# Sheet1.net
KiCad netlist of a schematic drawn in Altium Designer
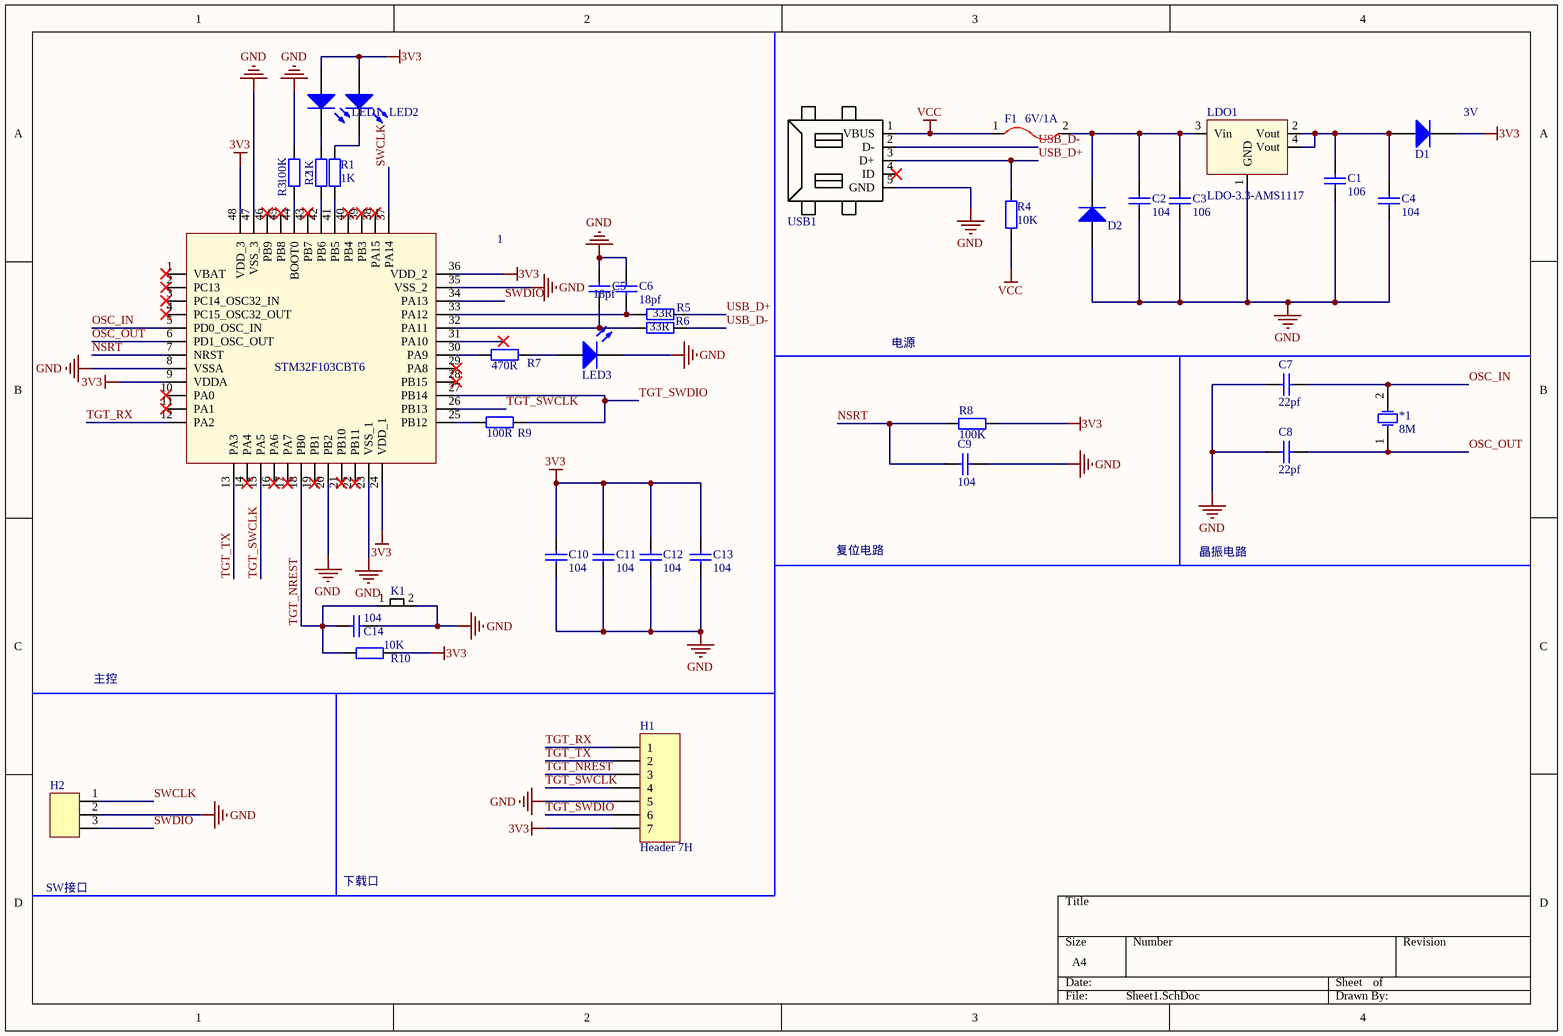
[diagram p0: Sheet1.SchDoc]

(export (version "E")
  (design (tool "Eeschema 10.0.6"))
  (components
    (comp (ref "*1") (value "8M") (footprint "XTAL_SMD_49S") (libsource (lib "DG") (part "XTAL_SMD")))
    (comp (ref "1")
      (value "STM32F103CBT6")
      (footprint "LQFP_48_7X7")
      (libsource (lib "DG") (part "STM32F103CBT6"))
    )
    (comp (ref "C1") (value "106") (footprint "C_SOP_1206") (libsource (lib "DG") (part "C_SMD")))
    (comp (ref "C2") (value "104") (footprint "C_SOP_0603") (libsource (lib "DG") (part "C_SMD")))
    (comp (ref "C3") (value "106") (footprint "C_SOP_1206") (libsource (lib "DG") (part "C_SMD")))
    (comp (ref "C4") (value "104") (footprint "C_SOP_0603") (libsource (lib "DG") (part "C_SMD")))
    (comp (ref "C5") (value "18pf") (footprint "C_SOP_0603") (libsource (lib "DG") (part "C_SMD")))
    (comp (ref "C6") (value "18pf") (footprint "C_SOP_0603") (libsource (lib "DG") (part "C_SMD")))
    (comp (ref "C7") (value "22pf") (footprint "C_SOP_0603") (libsource (lib "DG") (part "C_SMD")))
    (comp (ref "C8") (value "22pf") (footprint "C_SOP_0603") (libsource (lib "DG") (part "C_SMD")))
    (comp (ref "C9") (value "104") (footprint "C_SOP_0603") (libsource (lib "DG") (part "C_SMD")))
    (comp (ref "C10") (value "104") (footprint "C_SOP_0603") (libsource (lib "DG") (part "C_SMD")))
    (comp (ref "C11") (value "104") (footprint "C_SOP_0603") (libsource (lib "DG") (part "C_SMD")))
    (comp (ref "C12") (value "104") (footprint "C_SOP_0603") (libsource (lib "DG") (part "C_SMD")))
    (comp (ref "C13") (value "104") (footprint "C_SOP_0603") (libsource (lib "DG") (part "C_SMD")))
    (comp (ref "C14") (value "104") (footprint "C_SOP_0603") (libsource (lib "DG") (part "C_SMD")))
    (comp (ref "D1")
      (value "1N4007")
      (footprint "LC-SMA(DO-214AC)_S5")
      (libsource (lib "DG") (part "1N4007"))
    )
    (comp (ref "D2")
      (value "1N4007")
      (footprint "LC-SMA(DO-214AC)_S5")
      (libsource (lib "DG") (part "1N4007"))
    )
    (comp (ref "F1") (value "6V/1A") (footprint "Fuse_0805") (libsource (lib "DG") (part "FUSE")))
    (comp (ref "H1")
      (value "Header 7H")
      (footprint "Header 2.54X7")
      (description "Header, 7-Pin, Right Angle")
      (fields (field (name "PUBLISHER") "Altium Limited"))
      (libsource (lib "Miscellaneous Connectors") (part "Header 7H"))
    )
    (comp (ref "H2")
      (value "Header_1*3")
      (footprint "Header 2.54X3")
      (libsource (lib "DG") (part "Header_1*3"))
    )
    (comp (ref "K1") (value "KEY") (footprint "SW_PB_3X6") (libsource (lib "DG") (part "KEY")))
    (comp (ref "LDO1")
      (value "LDO-3.3-AMS1117")
      (footprint "SOT223_3")
      (libsource (lib "DG") (part "LDO-3.3-AMS1117"))
    )
    (comp (ref "LED1") (value "LED") (footprint "LED_0603_R") (libsource (lib "DG") (part "LED")))
    (comp (ref "LED2") (value "LED") (footprint "LED_0603_R") (libsource (lib "DG") (part "LED")))
    (comp (ref "LED3") (value "LED") (footprint "LED_0603_R") (libsource (lib "DG") (part "LED")))
    (comp (ref "R1") (value "1K") (footprint "R_SMD_0603") (libsource (lib "") (part "R_SMD_1")))
    (comp (ref "R2") (value "1K") (footprint "R_SMD_0603") (libsource (lib "") (part "R_SMD_1")))
    (comp (ref "R3") (value "100K") (footprint "R_SMD_0603") (libsource (lib "") (part "R_SMD_1")))
    (comp (ref "R4") (value "10K") (footprint "R_SMD_0603") (libsource (lib "") (part "R_SMD_1")))
    (comp (ref "R5") (value "33R") (footprint "R_SMD_0603") (libsource (lib "DG") (part "R_SMD")))
    (comp (ref "R6") (value "33R") (footprint "R_SMD_0603") (libsource (lib "DG") (part "R_SMD")))
    (comp (ref "R7") (value "470R") (footprint "R_SMD_0603") (libsource (lib "DG") (part "R_SMD")))
    (comp (ref "R8") (value "100K") (footprint "R_SMD_0603") (libsource (lib "DG") (part "R_SMD")))
    (comp (ref "R9") (value "100R") (footprint "R_SMD_0603") (libsource (lib "DG") (part "R_SMD")))
    (comp (ref "R10") (value "10K") (footprint "R_SMD_0603") (libsource (lib "DG") (part "R_SMD")))
    (comp (ref "USB1") (value "USB_AB") (footprint "USB_MINI_SMD") (libsource (lib "DG") (part "USB_AB")))
  )
  (nets
    (net (code "1") (name "/NSRT") (class "Default")
      (node (ref "1") (pin "7") (pinfunction "NRST_7") (pintype "passive"))
      (node (ref "C9") (pin "1") (pinfunction "1_1") (pintype "passive"))
      (node (ref "R8") (pin "1") (pinfunction "1_1") (pintype "passive"))
    )
    (net (code "2") (name "/OSC_IN") (class "Default")
      (node (ref "*1") (pin "2") (pinfunction "OSC2_2") (pintype "passive"))
      (node (ref "1") (pin "5") (pinfunction "PD0_OSC_IN_5") (pintype "passive"))
      (node (ref "C7") (pin "2") (pinfunction "2_2") (pintype "passive"))
    )
    (net (code "3") (name "/OSC_OUT") (class "Default")
      (node (ref "*1") (pin "1") (pinfunction "OSC1_1") (pintype "passive"))
      (node (ref "1") (pin "6") (pinfunction "PD1_OSC_OUT_6") (pintype "passive"))
      (node (ref "C8") (pin "2") (pinfunction "2_2") (pintype "passive"))
    )
    (net (code "4") (name "/SWCLK") (class "Default")
      (node (ref "1") (pin "37") (pinfunction "PA14_37") (pintype "passive"))
      (node (ref "H2") (pin "1") (pinfunction "1_1") (pintype "passive"))
    )
    (net (code "5") (name "/SWDIO") (class "Default")
      (node (ref "1") (pin "34") (pinfunction "PA13_34") (pintype "passive"))
      (node (ref "H2") (pin "3") (pinfunction "3_3") (pintype "passive"))
    )
    (net (code "6") (name "/TGT_NREST") (class "Default")
      (node (ref "1") (pin "18") (pinfunction "PB0_18") (pintype "passive"))
      (node (ref "C14") (pin "1") (pinfunction "1_1") (pintype "passive"))
      (node (ref "H1") (pin "3") (pinfunction "3_3") (pintype "passive"))
      (node (ref "K1") (pin "1") (pinfunction "*_1") (pintype "passive"))
      (node (ref "R10") (pin "1") (pinfunction "1_1") (pintype "passive"))
    )
    (net (code "7") (name "/TGT_RX") (class "Default")
      (node (ref "1") (pin "12") (pinfunction "PA2_12") (pintype "passive"))
      (node (ref "H1") (pin "1") (pinfunction "1_1") (pintype "passive"))
    )
    (net (code "8") (name "/TGT_SWCLK") (class "Default")
      (node (ref "1") (pin "15") (pinfunction "PA5_15") (pintype "passive"))
      (node (ref "1") (pin "26") (pinfunction "PB13_26") (pintype "passive"))
      (node (ref "H1") (pin "4") (pinfunction "4_4") (pintype "passive"))
    )
    (net (code "9") (name "/TGT_SWDIO") (class "Default")
      (node (ref "1") (pin "27") (pinfunction "PB14_27") (pintype "passive"))
      (node (ref "H1") (pin "6") (pinfunction "6_6") (pintype "passive"))
      (node (ref "R9") (pin "2") (pinfunction "2_2") (pintype "passive"))
    )
    (net (code "10") (name "/TGT_TX") (class "Default")
      (node (ref "1") (pin "13") (pinfunction "PA3_13") (pintype "passive"))
      (node (ref "H1") (pin "2") (pinfunction "2_2") (pintype "passive"))
    )
    (net (code "11") (name "/USB_D+") (class "Default")
      (node (ref "R4") (pin "2") (pinfunction "2_2") (pintype "passive"))
      (node (ref "R5") (pin "2") (pinfunction "2_2") (pintype "passive"))
      (node (ref "USB1") (pin "3") (pinfunction "D+_3") (pintype "passive"))
    )
    (net (code "12") (name "/USB_D-") (class "Default")
      (node (ref "R6") (pin "2") (pinfunction "2_2") (pintype "passive"))
      (node (ref "USB1") (pin "2") (pinfunction "D-_2") (pintype "passive"))
    )
    (net (code "13") (name "3V3") (class "Default")
      (node (ref "1") (pin "24") (pinfunction "VDD_1_24") (pintype "passive"))
      (node (ref "1") (pin "36") (pinfunction "VDD_2_36") (pintype "passive"))
      (node (ref "1") (pin "48") (pinfunction "VDD_3_48") (pintype "passive"))
      (node (ref "1") (pin "9") (pinfunction "VDDA_9") (pintype "passive"))
      (node (ref "C10") (pin "2") (pinfunction "2_2") (pintype "passive"))
      (node (ref "C11") (pin "2") (pinfunction "2_2") (pintype "passive"))
      (node (ref "C12") (pin "2") (pinfunction "2_2") (pintype "passive"))
      (node (ref "C13") (pin "2") (pinfunction "2_2") (pintype "passive"))
      (node (ref "D1") (pin "2") (pinfunction "K_2") (pintype "passive"))
      (node (ref "H1") (pin "7") (pinfunction "7_7") (pintype "passive"))
      (node (ref "LED1") (pin "1") (pinfunction "A_1") (pintype "passive"))
      (node (ref "LED2") (pin "1") (pinfunction "A_1") (pintype "passive"))
      (node (ref "R10") (pin "2") (pinfunction "2_2") (pintype "passive"))
      (node (ref "R8") (pin "2") (pinfunction "2_2") (pintype "passive"))
    )
    (net (code "14") (name "GND") (class "Default")
      (node (ref "1") (pin "20") (pinfunction "PB2_20") (pintype "passive"))
      (node (ref "1") (pin "23") (pinfunction "VSS_1_23") (pintype "passive"))
      (node (ref "1") (pin "35") (pinfunction "VSS_2_35") (pintype "passive"))
      (node (ref "1") (pin "47") (pinfunction "VSS_3_47") (pintype "passive"))
      (node (ref "1") (pin "8") (pinfunction "VSSA_8") (pintype "passive"))
      (node (ref "C1") (pin "1") (pinfunction "1_1") (pintype "passive"))
      (node (ref "C10") (pin "1") (pinfunction "1_1") (pintype "passive"))
      (node (ref "C11") (pin "1") (pinfunction "1_1") (pintype "passive"))
      (node (ref "C12") (pin "1") (pinfunction "1_1") (pintype "passive"))
      (node (ref "C13") (pin "1") (pinfunction "1_1") (pintype "passive"))
      (node (ref "C14") (pin "2") (pinfunction "2_2") (pintype "passive"))
      (node (ref "C2") (pin "1") (pinfunction "1_1") (pintype "passive"))
      (node (ref "C3") (pin "1") (pinfunction "1_1") (pintype "passive"))
      (node (ref "C4") (pin "1") (pinfunction "1_1") (pintype "passive"))
      (node (ref "C5") (pin "1") (pinfunction "1_1") (pintype "passive"))
      (node (ref "C6") (pin "1") (pinfunction "1_1") (pintype "passive"))
      (node (ref "C7") (pin "1") (pinfunction "1_1") (pintype "passive"))
      (node (ref "C8") (pin "1") (pinfunction "1_1") (pintype "passive"))
      (node (ref "C9") (pin "2") (pinfunction "2_2") (pintype "passive"))
      (node (ref "D2") (pin "1") (pinfunction "A_1") (pintype "passive"))
      (node (ref "H1") (pin "5") (pinfunction "5_5") (pintype "passive"))
      (node (ref "H2") (pin "2") (pinfunction "2_2") (pintype "passive"))
      (node (ref "K1") (pin "2") (pinfunction "*_2") (pintype "passive"))
      (node (ref "LDO1") (pin "1") (pinfunction "GND_1") (pintype "passive"))
      (node (ref "LED3") (pin "2") (pinfunction "K_2") (pintype "passive"))
      (node (ref "R3") (pin "2") (pinfunction "2_2") (pintype "passive"))
      (node (ref "USB1") (pin "5") (pinfunction "GND_5") (pintype "passive"))
    )
    (net (code "15") (name "Net-(1-BOOT0)") (class "Default")
      (node (ref "1") (pin "44") (pinfunction "BOOT0_44") (pintype "passive"))
      (node (ref "R3") (pin "1") (pinfunction "1_1") (pintype "passive"))
    )
    (net (code "16") (name "Net-(1-PA9)") (class "Default")
      (node (ref "1") (pin "30") (pinfunction "PA9_30") (pintype "passive"))
      (node (ref "R7") (pin "1") (pinfunction "1_1") (pintype "passive"))
    )
    (net (code "17") (name "Net-(1-PA11)") (class "Default")
      (node (ref "1") (pin "32") (pinfunction "PA11_32") (pintype "passive"))
      (node (ref "C5") (pin "2") (pinfunction "2_2") (pintype "passive"))
      (node (ref "R6") (pin "1") (pinfunction "1_1") (pintype "passive"))
    )
    (net (code "18") (name "Net-(1-PA12)") (class "Default")
      (node (ref "1") (pin "33") (pinfunction "PA12_33") (pintype "passive"))
      (node (ref "C6") (pin "2") (pinfunction "2_2") (pintype "passive"))
      (node (ref "R5") (pin "1") (pinfunction "1_1") (pintype "passive"))
    )
    (net (code "19") (name "Net-(1-PB5)") (class "Default")
      (node (ref "1") (pin "41") (pinfunction "PB5_41") (pintype "passive"))
      (node (ref "R1") (pin "1") (pinfunction "1_1") (pintype "passive"))
    )
    (net (code "20") (name "Net-(1-PB6)") (class "Default")
      (node (ref "1") (pin "42") (pinfunction "PB6_42") (pintype "passive"))
      (node (ref "R2") (pin "1") (pinfunction "1_1") (pintype "passive"))
    )
    (net (code "21") (name "Net-(1-PB12)") (class "Default")
      (node (ref "1") (pin "25") (pinfunction "PB12_25") (pintype "passive"))
      (node (ref "R9") (pin "1") (pinfunction "1_1") (pintype "passive"))
    )
    (net (code "22") (name "Net-(D1-A)") (class "Default")
      (node (ref "C1") (pin "2") (pinfunction "2_2") (pintype "passive"))
      (node (ref "C4") (pin "2") (pinfunction "2_2") (pintype "passive"))
      (node (ref "D1") (pin "1") (pinfunction "A_1") (pintype "passive"))
      (node (ref "LDO1") (pin "2") (pinfunction "Vout_2") (pintype "passive"))
      (node (ref "LDO1") (pin "4") (pinfunction "Vout_4") (pintype "passive"))
    )
    (net (code "23") (name "Net-(D2-K)") (class "Default")
      (node (ref "C2") (pin "2") (pinfunction "2_2") (pintype "passive"))
      (node (ref "C3") (pin "2") (pinfunction "2_2") (pintype "passive"))
      (node (ref "D2") (pin "2") (pinfunction "K_2") (pintype "passive"))
      (node (ref "F1") (pin "2") (pinfunction "OUT_2") (pintype "passive"))
      (node (ref "LDO1") (pin "3") (pinfunction "Vin_3") (pintype "passive"))
    )
    (net (code "24") (name "Net-(LED1-K)") (class "Default")
      (node (ref "LED1") (pin "2") (pinfunction "K_2") (pintype "passive"))
      (node (ref "R2") (pin "2") (pinfunction "2_2") (pintype "passive"))
    )
    (net (code "25") (name "Net-(LED2-K)") (class "Default")
      (node (ref "LED2") (pin "2") (pinfunction "K_2") (pintype "passive"))
      (node (ref "R1") (pin "2") (pinfunction "2_2") (pintype "passive"))
    )
    (net (code "26") (name "Net-(LED3-A)") (class "Default")
      (node (ref "LED3") (pin "1") (pinfunction "A_1") (pintype "passive"))
      (node (ref "R7") (pin "2") (pinfunction "2_2") (pintype "passive"))
    )
    (net (code "27") (name "VCC") (class "Default")
      (node (ref "F1") (pin "1") (pinfunction "OUT_1") (pintype "passive"))
      (node (ref "R4") (pin "1") (pinfunction "1_1") (pintype "passive"))
      (node (ref "USB1") (pin "1") (pinfunction "VBUS_1") (pintype "passive"))
    )
    (net (code "28") (name "unconnected-(1-PA0-Pad10)") (class "Default")
      (node (ref "1") (pin "10") (pinfunction "PA0_10") (pintype "passive+no_connect"))
    )
    (net (code "29") (name "unconnected-(1-PA1-Pad11)") (class "Default")
      (node (ref "1") (pin "11") (pinfunction "PA1_11") (pintype "passive+no_connect"))
    )
    (net (code "30") (name "unconnected-(1-PA4-Pad14)") (class "Default")
      (node (ref "1") (pin "14") (pinfunction "PA4_14") (pintype "passive+no_connect"))
    )
    (net (code "31") (name "unconnected-(1-PA6-Pad16)") (class "Default")
      (node (ref "1") (pin "16") (pinfunction "PA6_16") (pintype "passive+no_connect"))
    )
    (net (code "32") (name "unconnected-(1-PA7-Pad17)") (class "Default")
      (node (ref "1") (pin "17") (pinfunction "PA7_17") (pintype "passive+no_connect"))
    )
    (net (code "33") (name "unconnected-(1-PA8-Pad29)") (class "Default")
      (node (ref "1") (pin "29") (pinfunction "PA8_29") (pintype "passive+no_connect"))
    )
    (net (code "34") (name "unconnected-(1-PA10-Pad31)") (class "Default")
      (node (ref "1") (pin "31") (pinfunction "PA10_31") (pintype "passive+no_connect"))
    )
    (net (code "35") (name "unconnected-(1-PA15-Pad38)") (class "Default")
      (node (ref "1") (pin "38") (pinfunction "PA15_38") (pintype "passive+no_connect"))
    )
    (net (code "36") (name "unconnected-(1-PB1-Pad19)") (class "Default")
      (node (ref "1") (pin "19") (pinfunction "PB1_19") (pintype "passive+no_connect"))
    )
    (net (code "37") (name "unconnected-(1-PB3-Pad39)") (class "Default")
      (node (ref "1") (pin "39") (pinfunction "PB3_39") (pintype "passive+no_connect"))
    )
    (net (code "38") (name "unconnected-(1-PB4-Pad40)") (class "Default")
      (node (ref "1") (pin "40") (pinfunction "PB4_40") (pintype "passive+no_connect"))
    )
    (net (code "39") (name "unconnected-(1-PB7-Pad43)") (class "Default")
      (node (ref "1") (pin "43") (pinfunction "PB7_43") (pintype "passive+no_connect"))
    )
    (net (code "40") (name "unconnected-(1-PB8-Pad45)") (class "Default")
      (node (ref "1") (pin "45") (pinfunction "PB8_45") (pintype "passive+no_connect"))
    )
    (net (code "41") (name "unconnected-(1-PB9-Pad46)") (class "Default")
      (node (ref "1") (pin "46") (pinfunction "PB9_46") (pintype "passive+no_connect"))
    )
    (net (code "42") (name "unconnected-(1-PB10-Pad21)") (class "Default")
      (node (ref "1") (pin "21") (pinfunction "PB10_21") (pintype "passive+no_connect"))
    )
    (net (code "43") (name "unconnected-(1-PB11-Pad22)") (class "Default")
      (node (ref "1") (pin "22") (pinfunction "PB11_22") (pintype "passive+no_connect"))
    )
    (net (code "44") (name "unconnected-(1-PB15-Pad28)") (class "Default")
      (node (ref "1") (pin "28") (pinfunction "PB15_28") (pintype "passive+no_connect"))
    )
    (net (code "45") (name "unconnected-(1-PC13-Pad2)") (class "Default")
      (node (ref "1") (pin "2") (pinfunction "PC13_2") (pintype "passive+no_connect"))
    )
    (net (code "46") (name "unconnected-(1-PC14_OSC32_IN-Pad3)") (class "Default")
      (node (ref "1") (pin "3") (pinfunction "PC14_OSC32_IN_3") (pintype "passive+no_connect"))
    )
    (net (code "47") (name "unconnected-(1-PC15_OSC32_OUT-Pad4)") (class "Default")
      (node (ref "1") (pin "4") (pinfunction "PC15_OSC32_OUT_4") (pintype "passive+no_connect"))
    )
    (net (code "48") (name "unconnected-(1-VBAT-Pad1)") (class "Default")
      (node (ref "1") (pin "1") (pinfunction "VBAT_1") (pintype "passive+no_connect"))
    )
    (net (code "49") (name "unconnected-(USB1-ID-Pad4)") (class "Default")
      (node (ref "USB1") (pin "4") (pinfunction "ID_4") (pintype "passive+no_connect"))
    )
  )
)
